# Dogalgaz_Sobasi_2020-07-29_17-51-27.net
KiCad netlist of a schematic drawn in EasyEDA
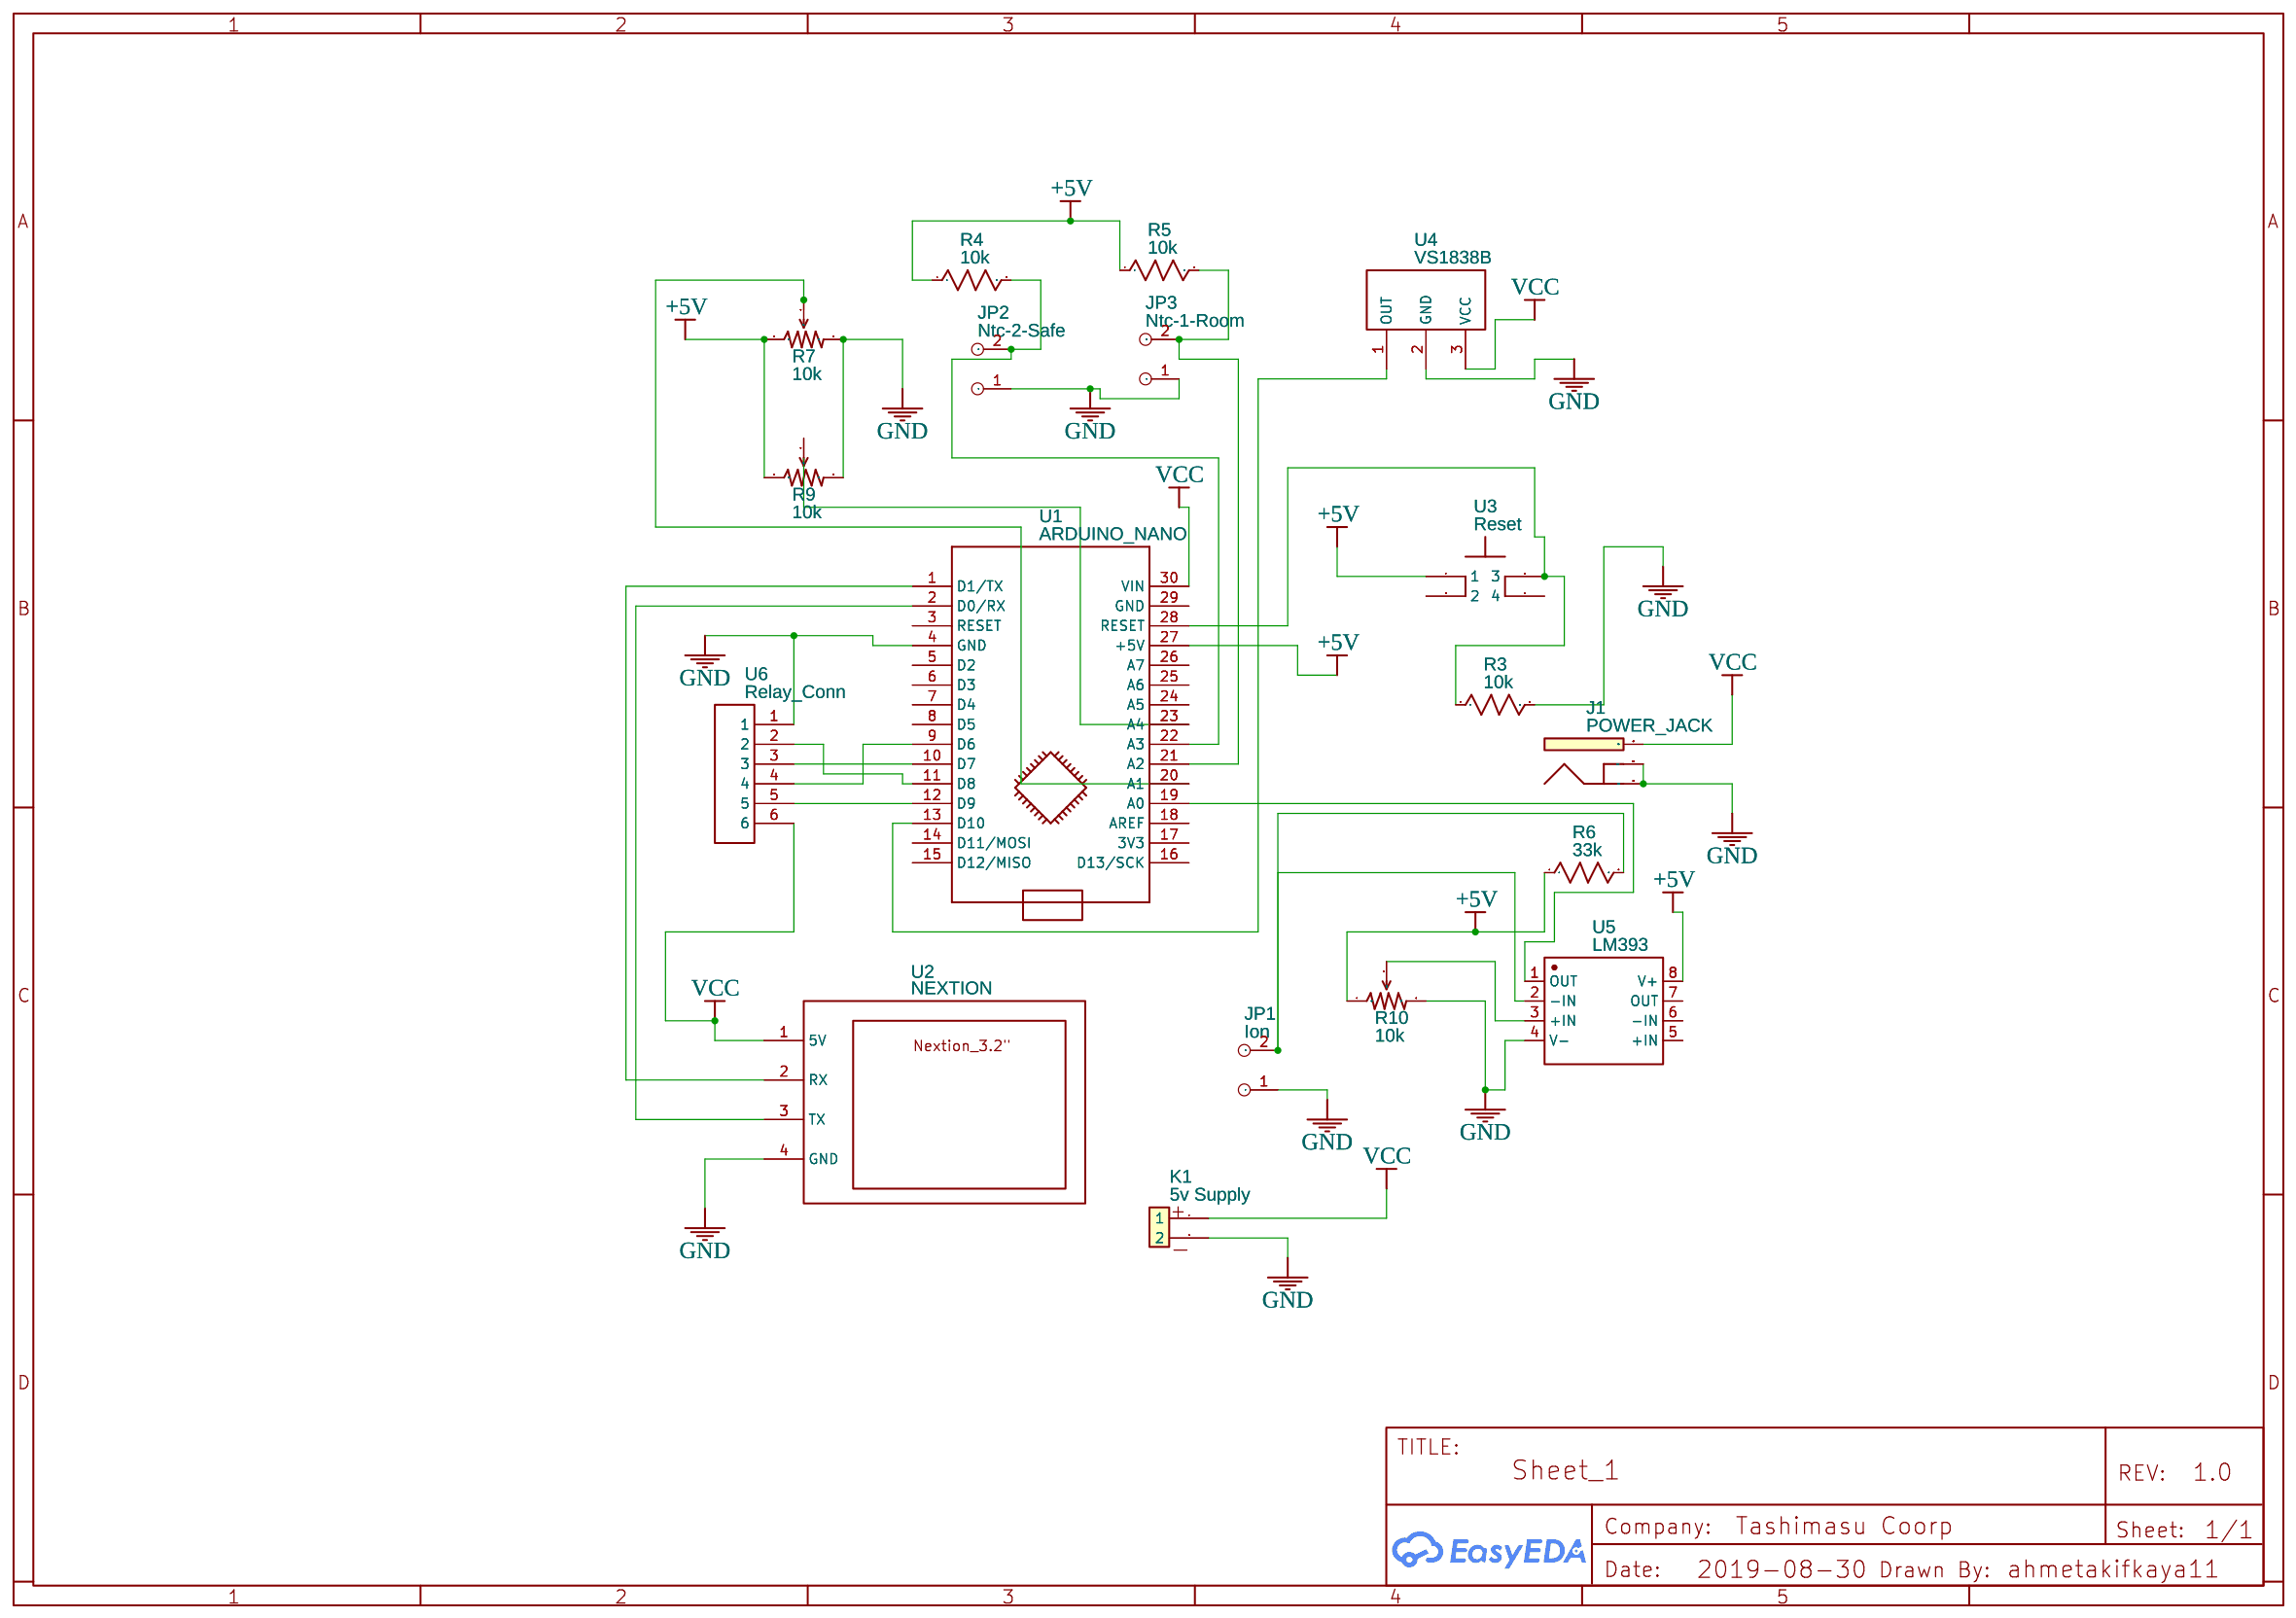
[diagram p0: schematic sheet]

(export (version "E")
  (design (tool "Eeschema 10.0.6"))
  (components
    (comp (ref "J1") (value "POWER_JACK") (libsource (lib "") (part "Unknown_800_380")))
    (comp (ref "JP1") (value "Ion") (libsource (lib "") (part "Unknown_630_545")))
    (comp (ref "JP2") (value "Ntc-2-Safe") (libsource (lib "") (part "Unknown_495_190")))
    (comp (ref "JP3") (value "Ntc-1-Room") (libsource (lib "") (part "Unknown_580_185")))
    (comp (ref "K1") (value "5v Supply") (libsource (lib "") (part "Unknown_585_620")))
    (comp (ref "R3") (value "10k") (libsource (lib "") (part "Res_AXIAL-0.3(1/8W)_US")))
    (comp (ref "R4") (value "10k") (libsource (lib "") (part "Res_AXIAL-0.3(1/8W)_US")))
    (comp (ref "R5") (value "10k") (libsource (lib "") (part "Res_AXIAL-0.3(1/8W)_US")))
    (comp (ref "R6") (value "33k") (libsource (lib "") (part "Res_AXIAL-0.3(1/8W)_US")))
    (comp (ref "R7") (value "10k") (libsource (lib "") (part "Unknown_400_155")))
    (comp (ref "R9") (value "10k") (libsource (lib "") (part "Unknown_400_225")))
    (comp (ref "R10") (value "10k") (libsource (lib "") (part "Unknown_695_490")))
    (comp (ref "U1") (value "ARDUINO_NANO") (libsource (lib "") (part "Unknown_525_365")))
    (comp (ref "U2")
      (value "NEXTION")
      (fields (field (name "BOM_Manufacturer Part") "NX3224T032"))
      (libsource (lib "") (part "Unknown_380_500"))
    )
    (comp (ref "U3")
      (value "Reset")
      (fields (field (name "BOM_Manufacturer Part") "Pushbutton"))
      (libsource (lib "") (part "Unknown_745_285"))
    )
    (comp (ref "U4") (value "VS1838B") (libsource (lib "") (part "Unknown_685_130")))
    (comp (ref "U5") (value "LM393") (libsource (lib "") (part "Unknown_805_505")))
    (comp (ref "U6") (value "Relay_Conn") (libsource (lib "") (part "Unknown_395_375")))
  )
  (nets
    (net (code "1") (name "+5V") (class "Default")
      (node (ref "R10") (pin "1") (pinfunction "CCW_1") (pintype "unspecified"))
      (node (ref "R4") (pin "1") (pinfunction "1_1") (pintype "unspecified"))
      (node (ref "R5") (pin "1") (pinfunction "1_1") (pintype "unspecified"))
      (node (ref "R6") (pin "1") (pinfunction "1_1") (pintype "unspecified"))
      (node (ref "R7") (pin "1") (pinfunction "CCW_1") (pintype "unspecified"))
      (node (ref "R9") (pin "1") (pinfunction "CCW_1") (pintype "unspecified"))
      (node (ref "U1") (pin "27") (pinfunction "+5V_27") (pintype "unspecified"))
      (node (ref "U3") (pin "1") (pinfunction "1_1") (pintype "unspecified"))
      (node (ref "U5") (pin "8") (pinfunction "V+_8") (pintype "unspecified"))
    )
    (net (code "2") (name "GND") (class "Default")
      (node (ref "J1") (pin "GND") (pinfunction "GND_GND") (pintype "unspecified"))
      (node (ref "J1") (pin "GNDBREAK") (pinfunction "GNDBREAK_GNDBREAK") (pintype "unspecified"))
      (node (ref "JP1") (pin "1") (pinfunction "1_1") (pintype "unspecified"))
      (node (ref "JP2") (pin "1") (pinfunction "1_1") (pintype "unspecified"))
      (node (ref "JP3") (pin "1") (pinfunction "1_1") (pintype "unspecified"))
      (node (ref "K1") (pin "2") (pinfunction "2_2") (pintype "unspecified"))
      (node (ref "R10") (pin "3") (pinfunction "CW_3") (pintype "unspecified"))
      (node (ref "R3") (pin "2") (pinfunction "2_2") (pintype "unspecified"))
      (node (ref "R7") (pin "3") (pinfunction "CW_3") (pintype "unspecified"))
      (node (ref "R9") (pin "3") (pinfunction "CW_3") (pintype "unspecified"))
      (node (ref "U1") (pin "4") (pinfunction "GND_4") (pintype "unspecified"))
      (node (ref "U2") (pin "4") (pinfunction "GND_4") (pintype "unspecified"))
      (node (ref "U4") (pin "2") (pinfunction "GND_2") (pintype "unspecified"))
      (node (ref "U5") (pin "4") (pinfunction "V-_4") (pintype "unspecified"))
      (node (ref "U6") (pin "1") (pinfunction "1_1") (pintype "unspecified"))
    )
    (net (code "3") (name "Net-(JP1-Pad2)") (class "Default")
      (node (ref "JP1") (pin "2") (pinfunction "2_2") (pintype "unspecified"))
      (node (ref "R6") (pin "2") (pinfunction "2_2") (pintype "unspecified"))
      (node (ref "U5") (pin "2") (pinfunction "-IN_2") (pintype "unspecified"))
    )
    (net (code "4") (name "Net-(R3-Pad1)") (class "Default")
      (node (ref "R3") (pin "1") (pinfunction "1_1") (pintype "unspecified"))
      (node (ref "U1") (pin "28") (pinfunction "RESET_28") (pintype "unspecified"))
      (node (ref "U3") (pin "3") (pinfunction "3_3") (pintype "unspecified"))
    )
    (net (code "5") (name "Net-(R7-WIPER)") (class "Default")
      (node (ref "R7") (pin "2") (pinfunction "WIPER_2") (pintype "unspecified"))
      (node (ref "U1") (pin "20") (pinfunction "A1_20") (pintype "unspecified"))
    )
    (net (code "6") (name "Net-(R9-WIPER)") (class "Default")
      (node (ref "R9") (pin "2") (pinfunction "WIPER_2") (pintype "unspecified"))
      (node (ref "U1") (pin "23") (pinfunction "A4_23") (pintype "unspecified"))
    )
    (net (code "7") (name "Net-(R10-WIPER)") (class "Default")
      (node (ref "R10") (pin "2") (pinfunction "WIPER_2") (pintype "unspecified"))
      (node (ref "U5") (pin "3") (pinfunction "+IN_3") (pintype "unspecified"))
    )
    (net (code "8") (name "Net-(U1-A0)") (class "Default")
      (node (ref "U1") (pin "19") (pinfunction "A0_19") (pintype "unspecified"))
      (node (ref "U5") (pin "1") (pinfunction "OUT_1") (pintype "unspecified"))
    )
    (net (code "9") (name "Net-(U1-A2)") (class "Default")
      (node (ref "JP3") (pin "2") (pinfunction "2_2") (pintype "unspecified"))
      (node (ref "R5") (pin "2") (pinfunction "2_2") (pintype "unspecified"))
      (node (ref "U1") (pin "21") (pinfunction "A2_21") (pintype "unspecified"))
    )
    (net (code "10") (name "Net-(U1-A3)") (class "Default")
      (node (ref "JP2") (pin "2") (pinfunction "2_2") (pintype "unspecified"))
      (node (ref "R4") (pin "2") (pinfunction "2_2") (pintype "unspecified"))
      (node (ref "U1") (pin "22") (pinfunction "A3_22") (pintype "unspecified"))
    )
    (net (code "11") (name "Net-(U1-D0{slash}RX)") (class "Default")
      (node (ref "U1") (pin "2") (pinfunction "D0/RX_2") (pintype "unspecified"))
      (node (ref "U2") (pin "3") (pinfunction "TX_3") (pintype "unspecified"))
    )
    (net (code "12") (name "Net-(U1-D1{slash}TX)") (class "Default")
      (node (ref "U1") (pin "1") (pinfunction "D1/TX_1") (pintype "unspecified"))
      (node (ref "U2") (pin "2") (pinfunction "RX_2") (pintype "unspecified"))
    )
    (net (code "13") (name "Net-(U1-D6)") (class "Default")
      (node (ref "U1") (pin "9") (pinfunction "D6_9") (pintype "unspecified"))
      (node (ref "U6") (pin "4") (pinfunction "4_4") (pintype "unspecified"))
    )
    (net (code "14") (name "Net-(U1-D7)") (class "Default")
      (node (ref "U1") (pin "10") (pinfunction "D7_10") (pintype "unspecified"))
      (node (ref "U6") (pin "3") (pinfunction "3_3") (pintype "unspecified"))
    )
    (net (code "15") (name "Net-(U1-D8)") (class "Default")
      (node (ref "U1") (pin "11") (pinfunction "D8_11") (pintype "unspecified"))
      (node (ref "U6") (pin "2") (pinfunction "2_2") (pintype "unspecified"))
    )
    (net (code "16") (name "Net-(U1-D9)") (class "Default")
      (node (ref "U1") (pin "12") (pinfunction "D9_12") (pintype "unspecified"))
      (node (ref "U6") (pin "5") (pinfunction "5_5") (pintype "unspecified"))
    )
    (net (code "17") (name "Net-(U1-D10)") (class "Default")
      (node (ref "U1") (pin "13") (pinfunction "D10_13") (pintype "unspecified"))
      (node (ref "U4") (pin "1") (pinfunction "OUT_1") (pintype "unspecified"))
    )
    (net (code "18") (name "VCC") (class "Default")
      (node (ref "J1") (pin "PWR") (pinfunction "PWR_PWR") (pintype "unspecified"))
      (node (ref "K1") (pin "1") (pinfunction "1_1") (pintype "unspecified"))
      (node (ref "U1") (pin "30") (pinfunction "VIN_30") (pintype "unspecified"))
      (node (ref "U2") (pin "1") (pinfunction "5V_1") (pintype "unspecified"))
      (node (ref "U4") (pin "3") (pinfunction "VCC_3") (pintype "unspecified"))
      (node (ref "U6") (pin "6") (pinfunction "6_6") (pintype "unspecified"))
    )
    (net (code "19") (name "unconnected-(U1-3V3-Pad17)") (class "Default")
      (node (ref "U1") (pin "17") (pinfunction "3V3_17") (pintype "unspecified"))
    )
    (net (code "20") (name "unconnected-(U1-A5-Pad24)") (class "Default")
      (node (ref "U1") (pin "24") (pinfunction "A5_24") (pintype "unspecified"))
    )
    (net (code "21") (name "unconnected-(U1-A6-Pad25)") (class "Default")
      (node (ref "U1") (pin "25") (pinfunction "A6_25") (pintype "unspecified"))
    )
    (net (code "22") (name "unconnected-(U1-A7-Pad26)") (class "Default")
      (node (ref "U1") (pin "26") (pinfunction "A7_26") (pintype "unspecified"))
    )
    (net (code "23") (name "unconnected-(U1-AREF-Pad18)") (class "Default")
      (node (ref "U1") (pin "18") (pinfunction "AREF_18") (pintype "unspecified"))
    )
    (net (code "24") (name "unconnected-(U1-D2-Pad5)") (class "Default")
      (node (ref "U1") (pin "5") (pinfunction "D2_5") (pintype "unspecified"))
    )
    (net (code "25") (name "unconnected-(U1-D3-Pad6)") (class "Default")
      (node (ref "U1") (pin "6") (pinfunction "D3_6") (pintype "unspecified"))
    )
    (net (code "26") (name "unconnected-(U1-D4-Pad7)") (class "Default")
      (node (ref "U1") (pin "7") (pinfunction "D4_7") (pintype "unspecified"))
    )
    (net (code "27") (name "unconnected-(U1-D5-Pad8)") (class "Default")
      (node (ref "U1") (pin "8") (pinfunction "D5_8") (pintype "unspecified"))
    )
    (net (code "28") (name "unconnected-(U1-D11{slash}MOSI-Pad14)") (class "Default")
      (node (ref "U1") (pin "14") (pinfunction "D11/MOSI_14") (pintype "unspecified"))
    )
    (net (code "29") (name "unconnected-(U1-D12{slash}MISO-Pad15)") (class "Default")
      (node (ref "U1") (pin "15") (pinfunction "D12/MISO_15") (pintype "unspecified"))
    )
    (net (code "30") (name "unconnected-(U1-D13{slash}SCK-Pad16)") (class "Default")
      (node (ref "U1") (pin "16") (pinfunction "D13/SCK_16") (pintype "unspecified"))
    )
    (net (code "31") (name "unconnected-(U1-GND-Pad29)") (class "Default")
      (node (ref "U1") (pin "29") (pinfunction "GND_29") (pintype "unspecified"))
    )
    (net (code "32") (name "unconnected-(U1-RESET-Pad3)") (class "Default")
      (node (ref "U1") (pin "3") (pinfunction "RESET_3") (pintype "unspecified"))
    )
    (net (code "33") (name "unconnected-(U3-Pad2)") (class "Default")
      (node (ref "U3") (pin "2") (pinfunction "2_2") (pintype "unspecified"))
    )
    (net (code "34") (name "unconnected-(U3-Pad4)") (class "Default")
      (node (ref "U3") (pin "4") (pinfunction "4_4") (pintype "unspecified"))
    )
    (net (code "35") (name "unconnected-(U5-+IN-Pad5)") (class "Default")
      (node (ref "U5") (pin "5") (pinfunction "+IN_5") (pintype "unspecified"))
    )
    (net (code "36") (name "unconnected-(U5--IN-Pad6)") (class "Default")
      (node (ref "U5") (pin "6") (pinfunction "-IN_6") (pintype "unspecified"))
    )
    (net (code "37") (name "unconnected-(U5-OUT-Pad7)") (class "Default")
      (node (ref "U5") (pin "7") (pinfunction "OUT_7") (pintype "unspecified"))
    )
  )
)
